# KickerManager.net
KiCad netlist of a schematic drawn in Altium Designer
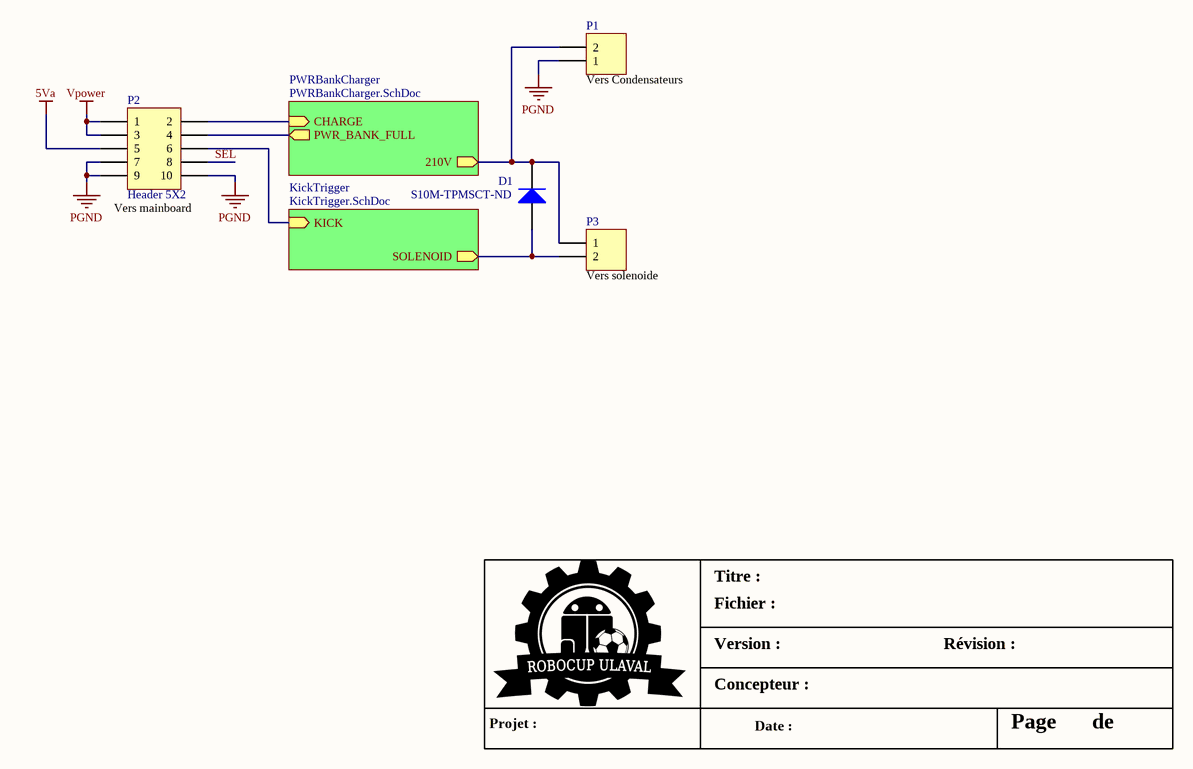
[diagram p0: KickerManager.SchDoc]

(export (version "E")
  (design (tool "Eeschema 10.0.6"))
  (components
    (comp (ref "D1")
      (value "S10M-TP")
      (footprint "HSMC")
      (description "DIODE GEN PURP 1KV 10A DO214AB")
      (fields
        (field (name "MANUFACTURER") "Micro Commercial Co")
        (field (name "SUPPLIER PART NUMBER 1") "S10M-TPMSCT-ND")
      )
      (libsource (lib "gamma_kicker") (part "S10M-TP"))
    )
    (comp (ref "P1")
      (value "Header 2")
      (footprint "0.156mil 2pin header")
      (description "Header, 2-Pin, 0.156mil")
      (libsource (lib "") (part "Header 2pin 0.156_1"))
    )
    (comp (ref "P2")
      (value "Header 5X2")
      (footprint "HDR2X5")
      (description "Header, 5-Pin, Dual row")
      (fields (field (name "PUBLISHER") "Altium Limited"))
      (libsource (lib "Miscellaneous Connectors") (part "Header 5X2"))
    )
    (comp (ref "P3")
      (value "Header 2")
      (footprint "0.156mil 2pin header")
      (description "Header, 2-Pin, 0.156mil")
      (libsource (lib "gamma_gestionkicker") (part "Header 2pin 0.156"))
    )
  )
  (nets
    (net (code "1") (name "/210V") (class "Default")
      (node (ref "D1") (pin "K") (pinfunction "K_K") (pintype "passive"))
      (node (ref "P1") (pin "2") (pinfunction "2_2") (pintype "passive"))
      (node (ref "P3") (pin "1") (pinfunction "1_1") (pintype "passive"))
    )
    (net (code "2") (name "/CHARGE") (class "Default")
      (node (ref "P2") (pin "2") (pinfunction "2_2") (pintype "passive"))
    )
    (net (code "3") (name "/KICK") (class "Default")
      (node (ref "P2") (pin "6") (pinfunction "6_6") (pintype "passive"))
    )
    (net (code "4") (name "/PWR_BANK_FULL") (class "Default")
      (node (ref "P2") (pin "4") (pinfunction "4_4") (pintype "passive"))
    )
    (net (code "5") (name "/SEL") (class "Default")
      (node (ref "P2") (pin "8") (pinfunction "8_8") (pintype "passive"))
    )
    (net (code "6") (name "/SOLENOID") (class "Default")
      (node (ref "D1") (pin "A") (pinfunction "A_A") (pintype "passive"))
      (node (ref "P3") (pin "2") (pinfunction "2_2") (pintype "passive"))
    )
    (net (code "7") (name "5Va") (class "Default")
      (node (ref "P2") (pin "5") (pinfunction "5_5") (pintype "passive"))
    )
    (net (code "8") (name "PGND") (class "Default")
      (node (ref "P1") (pin "1") (pinfunction "1_1") (pintype "passive"))
      (node (ref "P2") (pin "10") (pinfunction "10_10") (pintype "passive"))
      (node (ref "P2") (pin "7") (pinfunction "7_7") (pintype "passive"))
      (node (ref "P2") (pin "9") (pinfunction "9_9") (pintype "passive"))
    )
    (net (code "9") (name "Vpower") (class "Default")
      (node (ref "P2") (pin "1") (pinfunction "1_1") (pintype "passive"))
      (node (ref "P2") (pin "3") (pinfunction "3_3") (pintype "passive"))
    )
  )
)
